# Peripherals.net
KiCad netlist of a schematic drawn in EAGLE
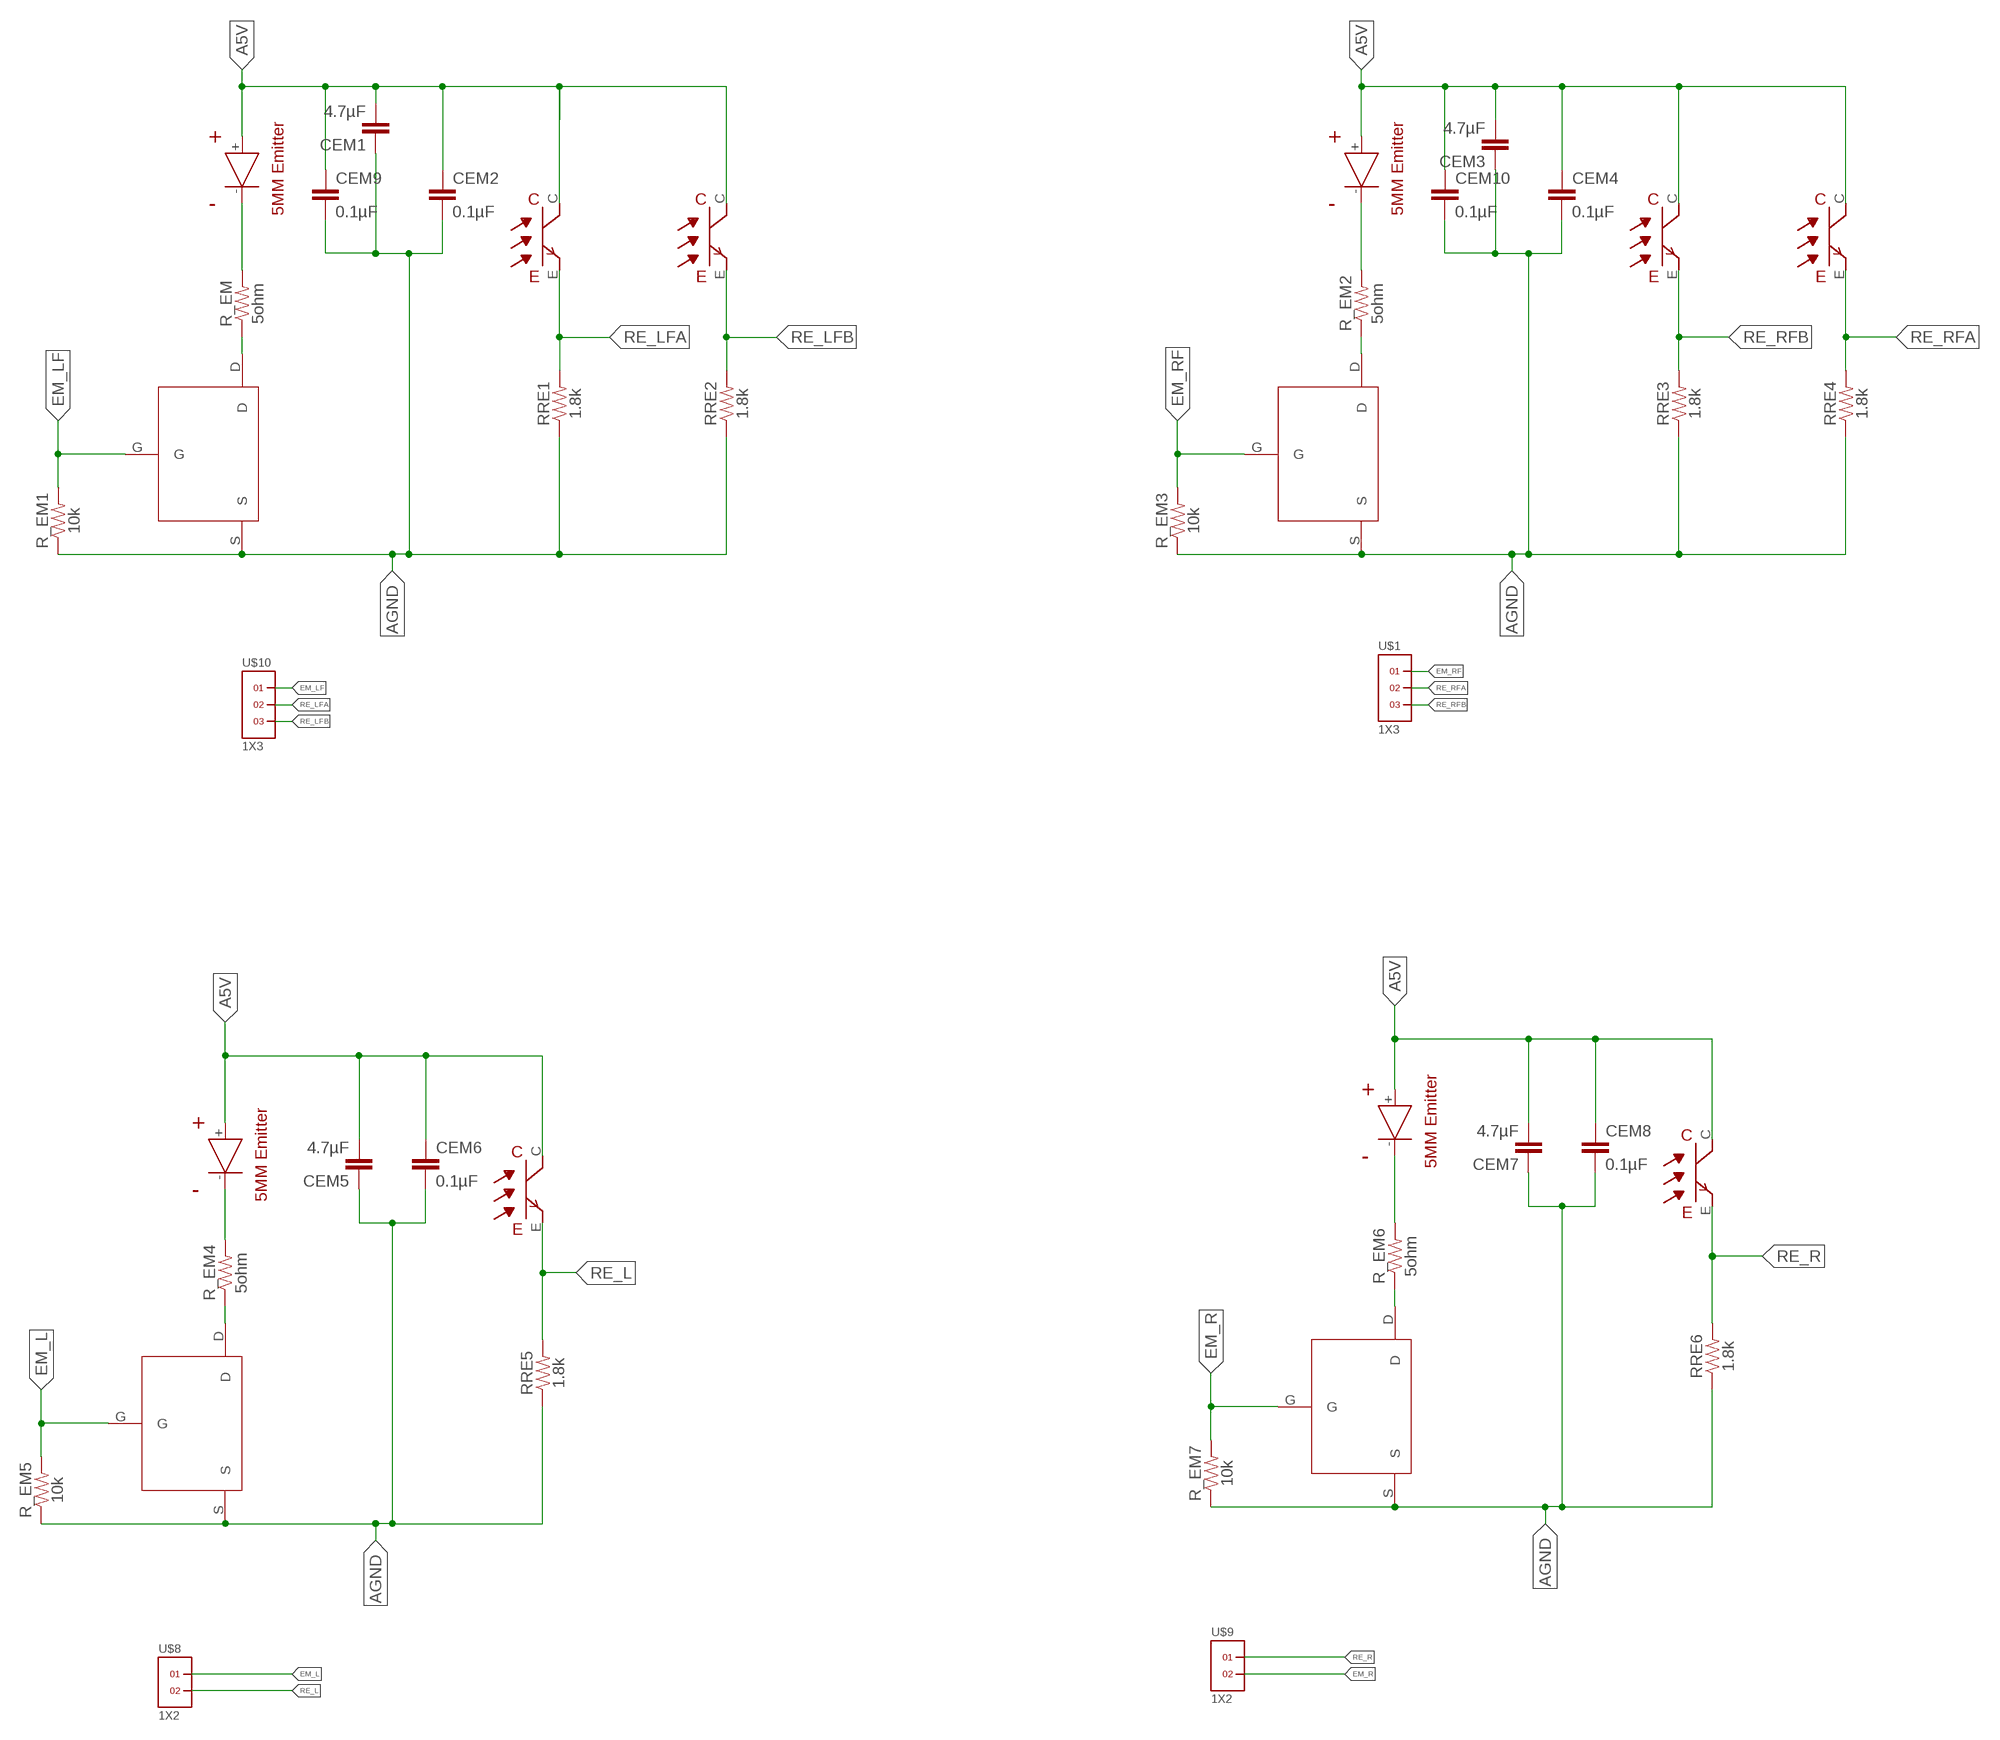
[diagram p0: schematic, sheet 1, part 1 of 2]
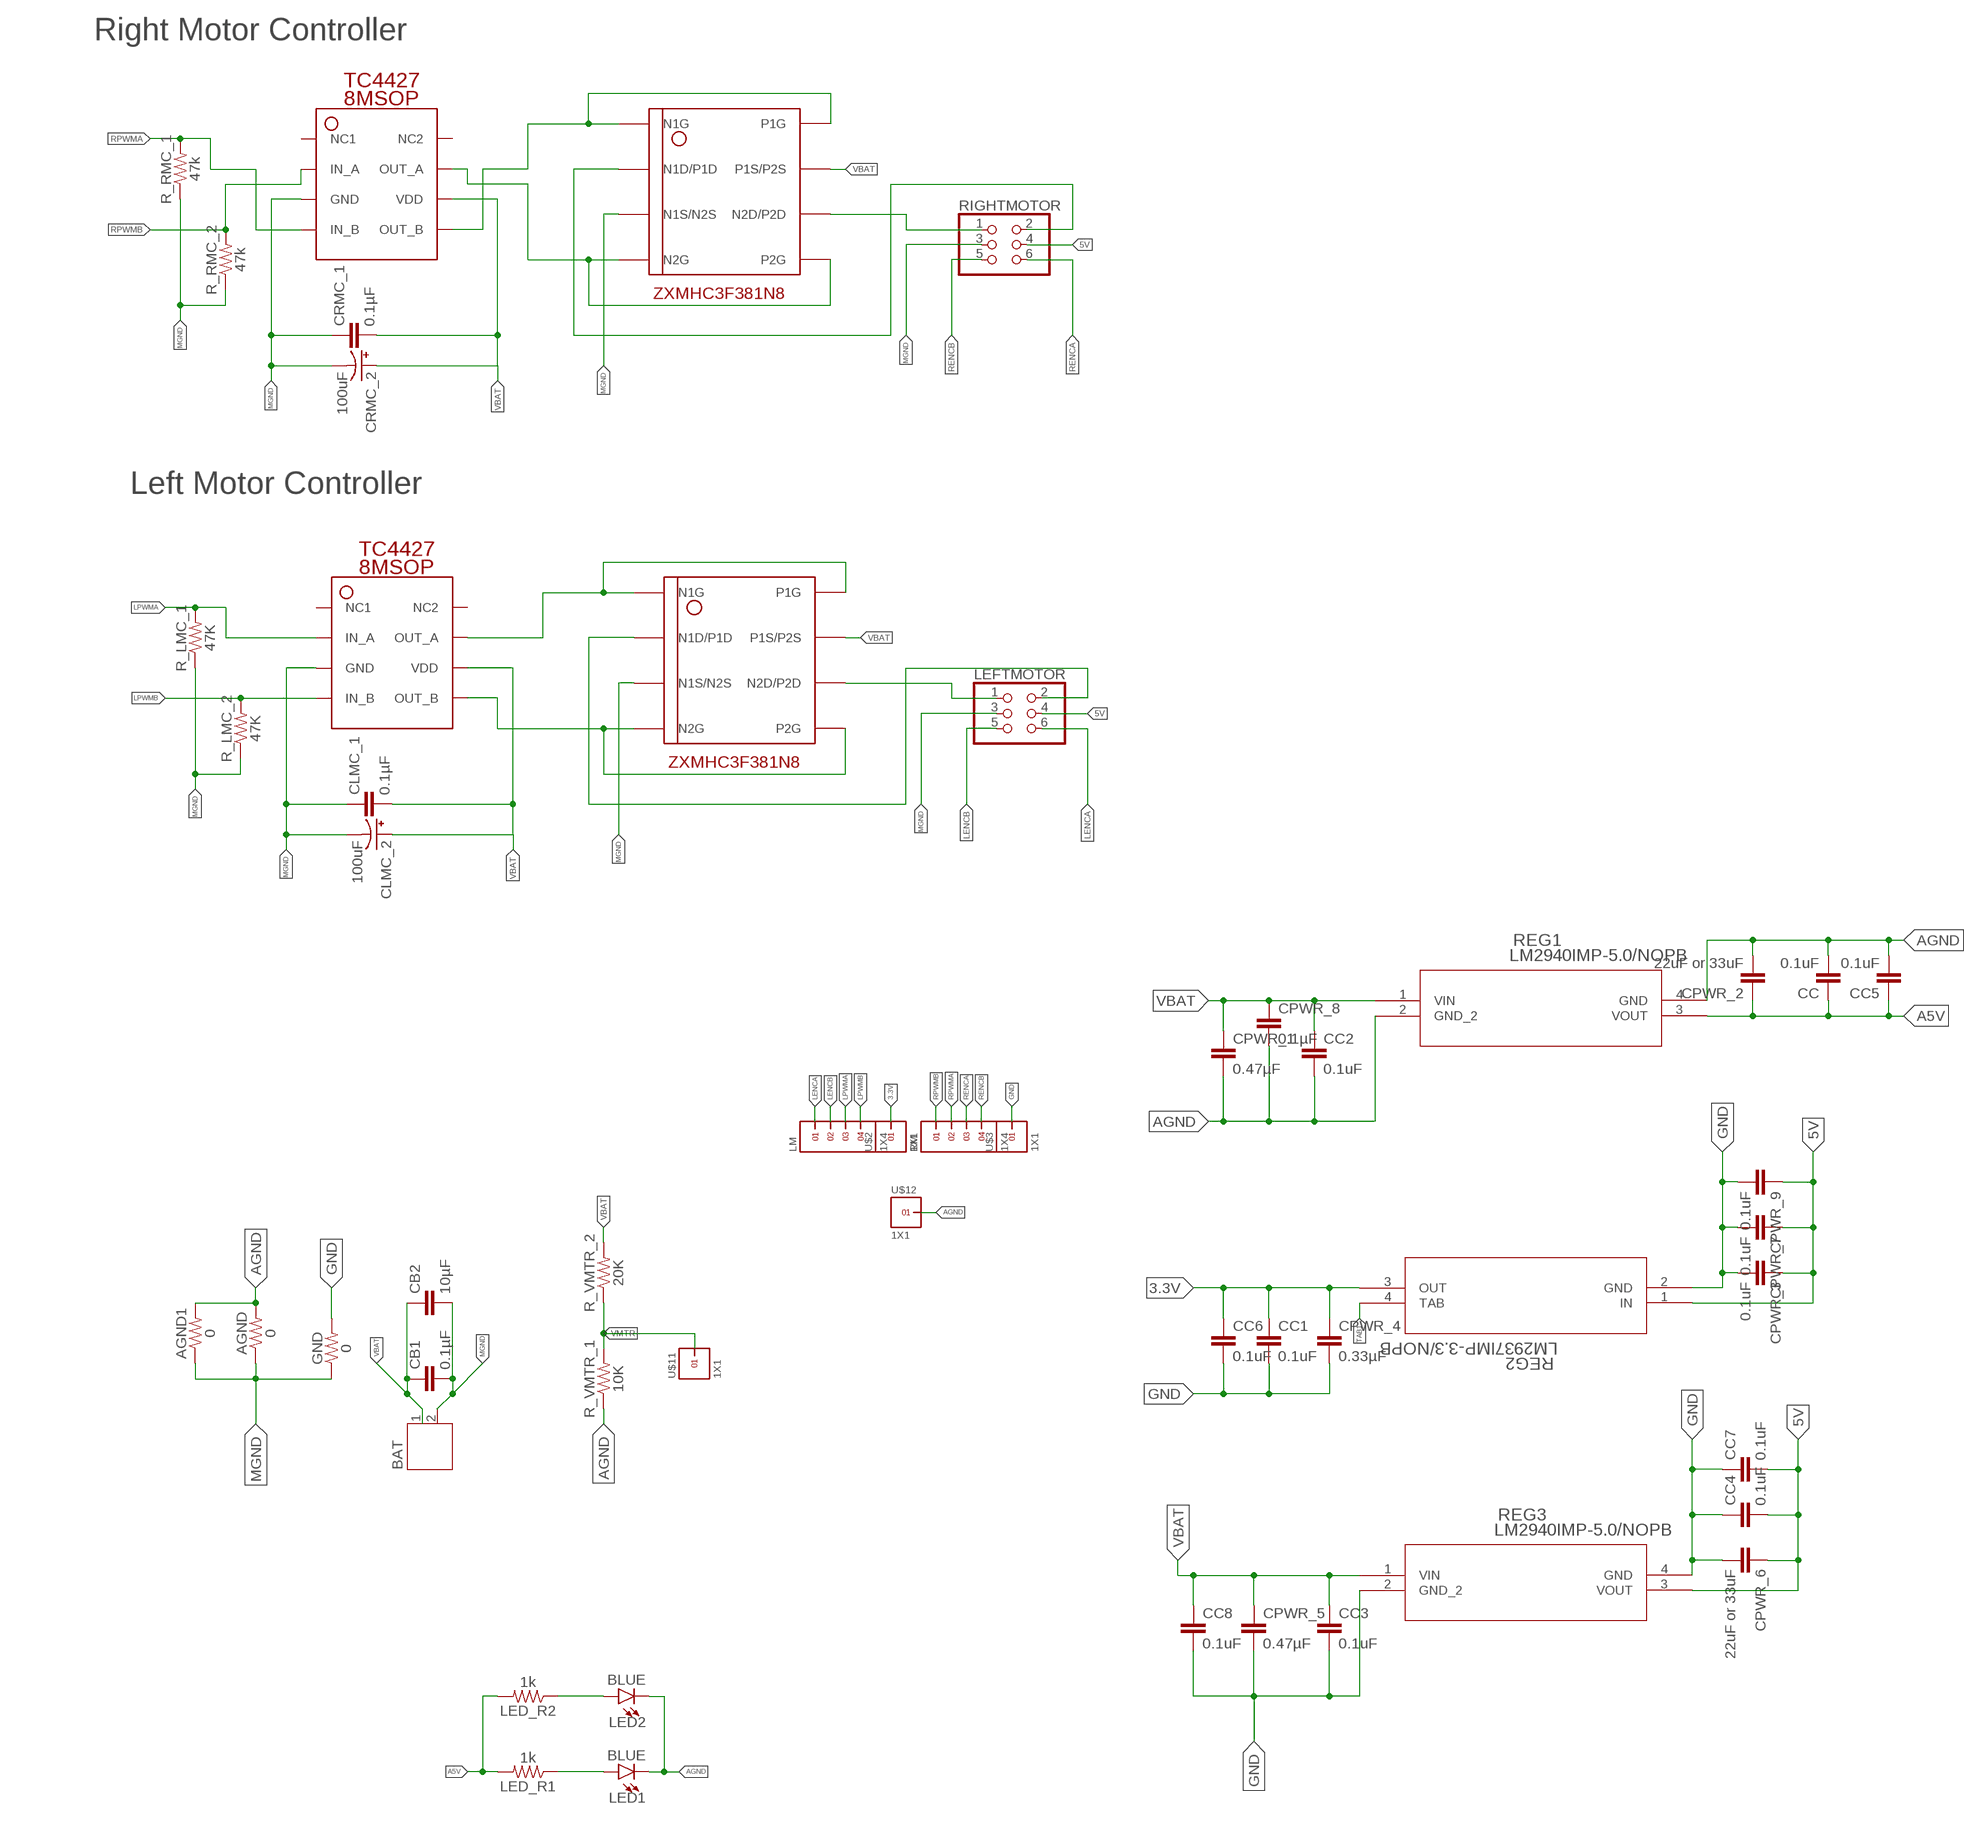
[diagram p1: schematic, sheet 1, part 2 of 2]

(export (version "E")
  (design (tool "Eeschema 10.0.6"))
  (components
    (comp (ref "AGND")
      (value "0")
      (footprint "eagle-import:0805")
      (libsource (lib "eagle-import") (part "SparkFun-Resistors_532_0.75OHM-0805-1/4W-1%"))
    )
    (comp (ref "AGND1")
      (value "0")
      (footprint "eagle-import:0805")
      (libsource (lib "eagle-import") (part "SparkFun-Resistors_532_0.75OHM-0805-1/4W-1%"))
    )
    (comp (ref "BAT")
      (value "JST-PH2")
      (footprint "eagle-import:JST-PH2")
      (libsource (lib "eagle-import") (part "JST-PH2"))
    )
    (comp (ref "CB1")
      (value "0.1µF")
      (footprint "eagle-import:0805")
      (libsource (lib "eagle-import") (part "SparkFun-Capacitors_510_0.33UF/330NF-0805-50V-10%"))
    )
    (comp (ref "CB2")
      (value "10µF")
      (footprint "eagle-import:0805")
      (libsource (lib "eagle-import") (part "SparkFun-Capacitors_510_0.33UF/330NF-0805-50V-10%"))
    )
    (comp (ref "CC")
      (value "0.1uF")
      (footprint "eagle-import:0805")
      (libsource (lib "eagle-import") (part "0.33UF/330NF-0805-50V-10%"))
    )
    (comp (ref "CC1")
      (value "0.1uF")
      (footprint "eagle-import:0805")
      (libsource (lib "eagle-import") (part "0.33UF/330NF-0805-50V-10%"))
    )
    (comp (ref "CC2")
      (value "0.1uF")
      (footprint "eagle-import:0805")
      (libsource (lib "eagle-import") (part "0.33UF/330NF-0805-50V-10%"))
    )
    (comp (ref "CC3")
      (value "0.1uF")
      (footprint "eagle-import:0805")
      (libsource (lib "eagle-import") (part "0.33UF/330NF-0805-50V-10%"))
    )
    (comp (ref "CC4")
      (value "0.1uF")
      (footprint "eagle-import:0805")
      (libsource (lib "eagle-import") (part "0.33UF/330NF-0805-50V-10%"))
    )
    (comp (ref "CC5")
      (value "0.1uF")
      (footprint "eagle-import:0805")
      (libsource (lib "eagle-import") (part "0.33UF/330NF-0805-50V-10%"))
    )
    (comp (ref "CC6")
      (value "0.1uF")
      (footprint "eagle-import:0805")
      (libsource (lib "eagle-import") (part "0.33UF/330NF-0805-50V-10%"))
    )
    (comp (ref "CC7")
      (value "0.1uF")
      (footprint "eagle-import:0805")
      (libsource (lib "eagle-import") (part "0.33UF/330NF-0805-50V-10%"))
    )
    (comp (ref "CC8")
      (value "0.1uF")
      (footprint "eagle-import:0805")
      (libsource (lib "eagle-import") (part "0.33UF/330NF-0805-50V-10%"))
    )
    (comp (ref "CEM1")
      (value "4.7µF")
      (footprint "eagle-import:0805")
      (libsource (lib "eagle-import") (part "0.33UF/330NF-0805-50V-10%"))
    )
    (comp (ref "CEM2")
      (value "0.1µF")
      (footprint "eagle-import:0805")
      (libsource (lib "eagle-import") (part "0.33UF/330NF-0805-50V-10%"))
    )
    (comp (ref "CEM3")
      (value "4.7µF")
      (footprint "eagle-import:0805")
      (libsource (lib "eagle-import") (part "0.33UF/330NF-0805-50V-10%"))
    )
    (comp (ref "CEM4")
      (value "0.1µF")
      (footprint "eagle-import:0805")
      (libsource (lib "eagle-import") (part "0.33UF/330NF-0805-50V-10%"))
    )
    (comp (ref "CEM5")
      (value "4.7µF")
      (footprint "eagle-import:0805")
      (libsource (lib "eagle-import") (part "0.33UF/330NF-0805-50V-10%"))
    )
    (comp (ref "CEM6")
      (value "0.1µF")
      (footprint "eagle-import:0805")
      (libsource (lib "eagle-import") (part "0.33UF/330NF-0805-50V-10%"))
    )
    (comp (ref "CEM7")
      (value "4.7µF")
      (footprint "eagle-import:0805")
      (libsource (lib "eagle-import") (part "0.33UF/330NF-0805-50V-10%"))
    )
    (comp (ref "CEM8")
      (value "0.1µF")
      (footprint "eagle-import:0805")
      (libsource (lib "eagle-import") (part "0.33UF/330NF-0805-50V-10%"))
    )
    (comp (ref "CEM9")
      (value "0.1µF")
      (footprint "eagle-import:0805")
      (libsource (lib "eagle-import") (part "0.33UF/330NF-0805-50V-10%"))
    )
    (comp (ref "CEM10")
      (value "0.1µF")
      (footprint "eagle-import:0805")
      (libsource (lib "eagle-import") (part "0.33UF/330NF-0805-50V-10%"))
    )
    (comp (ref "CLMC_1")
      (value "0.1µF")
      (footprint "eagle-import:0805")
      (libsource (lib "eagle-import") (part "SparkFun-Capacitors_510_0.33UF/330NF-0805-50V-10%"))
    )
    (comp (ref "CLMC_2")
      (value "100uF")
      (footprint "eagle-import:EIA7343")
      (libsource (lib "eagle-import") (part "100UF-POLAR-EIA7343-10V-10%(TANT)"))
    )
    (comp (ref "CPWR_1")
      (value "0.47µF")
      (footprint "eagle-import:0805")
      (libsource (lib "eagle-import") (part "0.33UF/330NF-0805-50V-10%"))
    )
    (comp (ref "CPWR_2")
      (value "22uF or 33uF")
      (footprint "eagle-import:0805")
      (libsource (lib "eagle-import") (part "0.33UF/330NF-0805-50V-10%"))
    )
    (comp (ref "CPWR_3")
      (value "0.1uF")
      (footprint "eagle-import:0805")
      (libsource (lib "eagle-import") (part "0.33UF/330NF-0805-50V-10%"))
    )
    (comp (ref "CPWR_4")
      (value "0.33µF")
      (footprint "eagle-import:0805")
      (libsource (lib "eagle-import") (part "0.33UF/330NF-0805-50V-10%"))
    )
    (comp (ref "CPWR_5")
      (value "0.47µF")
      (footprint "eagle-import:0805")
      (libsource (lib "eagle-import") (part "0.33UF/330NF-0805-50V-10%"))
    )
    (comp (ref "CPWR_6")
      (value "22uF or 33uF")
      (footprint "eagle-import:0805")
      (libsource (lib "eagle-import") (part "0.33UF/330NF-0805-50V-10%"))
    )
    (comp (ref "CPWR_7")
      (value "0.1uF")
      (footprint "eagle-import:0805")
      (libsource (lib "eagle-import") (part "0.33UF/330NF-0805-50V-10%"))
    )
    (comp (ref "CPWR_8")
      (value "0.1µF")
      (footprint "eagle-import:0805")
      (libsource (lib "eagle-import") (part "0.33UF/330NF-0805-50V-10%"))
    )
    (comp (ref "CPWR_9")
      (value "0.1uF")
      (footprint "eagle-import:0805")
      (libsource (lib "eagle-import") (part "0.33UF/330NF-0805-50V-10%"))
    )
    (comp (ref "CRMC_1")
      (value "0.1µF")
      (footprint "eagle-import:0805")
      (libsource (lib "eagle-import") (part "SparkFun-Capacitors_510_0.33UF/330NF-0805-50V-10%"))
    )
    (comp (ref "CRMC_2")
      (value "100uF")
      (footprint "eagle-import:EIA7343")
      (libsource (lib "eagle-import") (part "100UF-POLAR-EIA7343-10V-10%(TANT)"))
    )
    (comp (ref "EM_L")
      (value "EMITTER")
      (footprint "eagle-import:EMITTER")
      (libsource (lib "eagle-import") (part "EMITTER"))
    )
    (comp (ref "EM_LF")
      (value "EMITTER")
      (footprint "eagle-import:EMITTER")
      (libsource (lib "eagle-import") (part "EMITTER"))
    )
    (comp (ref "EM_R")
      (value "EMITTER")
      (footprint "eagle-import:EMITTER")
      (libsource (lib "eagle-import") (part "EMITTER"))
    )
    (comp (ref "EM_RF")
      (value "EMITTER")
      (footprint "eagle-import:EMITTER")
      (libsource (lib "eagle-import") (part "EMITTER"))
    )
    (comp (ref "GND")
      (value "0")
      (footprint "eagle-import:0805")
      (libsource (lib "eagle-import") (part "SparkFun-Resistors_532_0.75OHM-0805-1/4W-1%"))
    )
    (comp (ref "LED1")
      (value "BLUE")
      (footprint "eagle-import:LED-1206")
      (libsource (lib "eagle-import") (part "LED-BLUE1206"))
    )
    (comp (ref "LED2")
      (value "BLUE")
      (footprint "eagle-import:LED-1206")
      (libsource (lib "eagle-import") (part "LED-BLUE1206"))
    )
    (comp (ref "LED_R1")
      (value "1k")
      (footprint "eagle-import:0805")
      (libsource (lib "eagle-import") (part "0.75OHM-0805-1/4W-1%"))
    )
    (comp (ref "LED_R2")
      (value "1k")
      (footprint "eagle-import:0805")
      (libsource (lib "eagle-import") (part "0.75OHM-0805-1/4W-1%"))
    )
    (comp (ref "LEFTMOTOR")
      (value "PINHD-2X3")
      (footprint "eagle-import:2X03")
      (libsource (lib "eagle-import") (part "PINHD-2X3"))
    )
    (comp (ref "LM")
      (value "1X4")
      (footprint "eagle-import:1X4")
      (libsource (lib "eagle-import") (part "1X4"))
    )
    (comp (ref "REG1")
      (value "LM2940IMP-5.0/NOPB")
      (footprint "eagle-import:MP04A")
      (fields
        (field (name "MANUFACTURER_PART_NUMBER") "LM2940IMP5.0NOPB")
        (field (name "COPYRIGHT") "Copyright C 2015 Accelerated Designs. All rights reserved")
      )
      (libsource (lib "eagle-import") (part "LM2940IMP-5.0/NOPB"))
    )
    (comp (ref "REG2")
      (value "LM2937IMP-3.3/NOPB")
      (footprint "eagle-import:MP04A")
      (fields
        (field (name "MANUFACTURER_PART_NUMBER") "lm2937imp3_3nopb")
        (field (name "COPYRIGHT") "Copyright C 2015 Accelerated Designs. All rights reserved")
      )
      (libsource (lib "eagle-import") (part "LM2937IMP-3.3/NOPB"))
    )
    (comp (ref "REG3")
      (value "LM2940IMP-5.0/NOPB")
      (footprint "eagle-import:MP04A")
      (fields
        (field (name "MANUFACTURER_PART_NUMBER") "LM2940IMP5.0NOPB")
        (field (name "COPYRIGHT") "Copyright C 2015 Accelerated Designs. All rights reserved")
      )
      (libsource (lib "eagle-import") (part "LM2940IMP-5.0/NOPB"))
    )
    (comp (ref "RE_L")
      (value "RECEIVER")
      (footprint "eagle-import:RECEIVER")
      (libsource (lib "eagle-import") (part "RECEIVER"))
    )
    (comp (ref "RE_LFA")
      (value "RECEIVER")
      (footprint "eagle-import:RECEIVER")
      (libsource (lib "eagle-import") (part "RECEIVER"))
    )
    (comp (ref "RE_LFB")
      (value "RECEIVER")
      (footprint "eagle-import:RECEIVER")
      (libsource (lib "eagle-import") (part "RECEIVER"))
    )
    (comp (ref "RE_R")
      (value "RECEIVER")
      (footprint "eagle-import:RECEIVER")
      (libsource (lib "eagle-import") (part "RECEIVER"))
    )
    (comp (ref "RE_RFA")
      (value "RECEIVER")
      (footprint "eagle-import:RECEIVER")
      (libsource (lib "eagle-import") (part "RECEIVER"))
    )
    (comp (ref "RE_RFB")
      (value "RECEIVER")
      (footprint "eagle-import:RECEIVER")
      (libsource (lib "eagle-import") (part "RECEIVER"))
    )
    (comp (ref "RIGHTMOTOR")
      (value "PINHD-2X3")
      (footprint "eagle-import:2X03")
      (libsource (lib "eagle-import") (part "PINHD-2X3"))
    )
    (comp (ref "RM")
      (value "1X4")
      (footprint "eagle-import:1X4")
      (libsource (lib "eagle-import") (part "1X4"))
    )
    (comp (ref "RRE1")
      (value "1.8k")
      (footprint "eagle-import:0805")
      (libsource (lib "eagle-import") (part "0.75OHM-0805-1/4W-1%"))
    )
    (comp (ref "RRE2")
      (value "1.8k")
      (footprint "eagle-import:0805")
      (libsource (lib "eagle-import") (part "0.75OHM-0805-1/4W-1%"))
    )
    (comp (ref "RRE3")
      (value "1.8k")
      (footprint "eagle-import:0805")
      (libsource (lib "eagle-import") (part "0.75OHM-0805-1/4W-1%"))
    )
    (comp (ref "RRE4")
      (value "1.8k")
      (footprint "eagle-import:0805")
      (libsource (lib "eagle-import") (part "0.75OHM-0805-1/4W-1%"))
    )
    (comp (ref "RRE5")
      (value "1.8k")
      (footprint "eagle-import:0805")
      (libsource (lib "eagle-import") (part "0.75OHM-0805-1/4W-1%"))
    )
    (comp (ref "RRE6")
      (value "1.8k")
      (footprint "eagle-import:0805")
      (libsource (lib "eagle-import") (part "0.75OHM-0805-1/4W-1%"))
    )
    (comp (ref "R_EM")
      (value "5ohm")
      (footprint "eagle-import:0805")
      (libsource (lib "eagle-import") (part "0.75OHM-0805-1/4W-1%"))
    )
    (comp (ref "R_EM1")
      (value "10k")
      (footprint "eagle-import:0805")
      (libsource (lib "eagle-import") (part "0.75OHM-0805-1/4W-1%"))
    )
    (comp (ref "R_EM2")
      (value "5ohm")
      (footprint "eagle-import:0805")
      (libsource (lib "eagle-import") (part "0.75OHM-0805-1/4W-1%"))
    )
    (comp (ref "R_EM3")
      (value "10k")
      (footprint "eagle-import:0805")
      (libsource (lib "eagle-import") (part "0.75OHM-0805-1/4W-1%"))
    )
    (comp (ref "R_EM4")
      (value "5ohm")
      (footprint "eagle-import:0805")
      (libsource (lib "eagle-import") (part "0.75OHM-0805-1/4W-1%"))
    )
    (comp (ref "R_EM5")
      (value "10k")
      (footprint "eagle-import:0805")
      (libsource (lib "eagle-import") (part "0.75OHM-0805-1/4W-1%"))
    )
    (comp (ref "R_EM6")
      (value "5ohm")
      (footprint "eagle-import:0805")
      (libsource (lib "eagle-import") (part "0.75OHM-0805-1/4W-1%"))
    )
    (comp (ref "R_EM7")
      (value "10k")
      (footprint "eagle-import:0805")
      (libsource (lib "eagle-import") (part "0.75OHM-0805-1/4W-1%"))
    )
    (comp (ref "R_LMC_1")
      (value "47K")
      (footprint "eagle-import:0805")
      (libsource (lib "eagle-import") (part "SparkFun-Resistors_532_0.75OHM-0805-1/4W-1%"))
    )
    (comp (ref "R_LMC_2")
      (value "47K")
      (footprint "eagle-import:0805")
      (libsource (lib "eagle-import") (part "SparkFun-Resistors_532_0.75OHM-0805-1/4W-1%"))
    )
    (comp (ref "R_RMC_1")
      (value "47k")
      (footprint "eagle-import:0805")
      (libsource (lib "eagle-import") (part "SparkFun-Resistors_532_0.75OHM-0805-1/4W-1%"))
    )
    (comp (ref "R_RMC_2")
      (value "47k")
      (footprint "eagle-import:0805")
      (libsource (lib "eagle-import") (part "SparkFun-Resistors_532_0.75OHM-0805-1/4W-1%"))
    )
    (comp (ref "R_VMTR_1")
      (value "10K")
      (footprint "eagle-import:0805")
      (libsource (lib "eagle-import") (part "0.75OHM-0805-1/4W-1%"))
    )
    (comp (ref "R_VMTR_2")
      (value "20K")
      (footprint "eagle-import:0805")
      (libsource (lib "eagle-import") (part "0.75OHM-0805-1/4W-1%"))
    )
    (comp (ref "U$1")
      (value "1X3")
      (footprint "eagle-import:1X3")
      (libsource (lib "eagle-import") (part "1X3"))
    )
    (comp (ref "U$2")
      (value "1X1")
      (footprint "eagle-import:1X1")
      (libsource (lib "eagle-import") (part "1X1"))
    )
    (comp (ref "U$3")
      (value "1X1")
      (footprint "eagle-import:1X1")
      (libsource (lib "eagle-import") (part "1X1"))
    )
    (comp (ref "U$4")
      (value "MCH3474")
      (footprint "eagle-import:MCH3474")
      (libsource (lib "eagle-import") (part "MCH3474"))
    )
    (comp (ref "U$5")
      (value "MCH3474")
      (footprint "eagle-import:MCH3474")
      (libsource (lib "eagle-import") (part "MCH3474"))
    )
    (comp (ref "U$6")
      (value "MCH3474")
      (footprint "eagle-import:MCH3474")
      (libsource (lib "eagle-import") (part "MCH3474"))
    )
    (comp (ref "U$7")
      (value "MCH3474")
      (footprint "eagle-import:MCH3474")
      (libsource (lib "eagle-import") (part "MCH3474"))
    )
    (comp (ref "U$8")
      (value "1X2")
      (footprint "eagle-import:1X2")
      (libsource (lib "eagle-import") (part "1X2"))
    )
    (comp (ref "U$9")
      (value "1X2")
      (footprint "eagle-import:1X2")
      (libsource (lib "eagle-import") (part "1X2"))
    )
    (comp (ref "U$10")
      (value "1X3")
      (footprint "eagle-import:1X3")
      (libsource (lib "eagle-import") (part "1X3"))
    )
    (comp (ref "U$11")
      (value "1X1")
      (footprint "eagle-import:1X1")
      (libsource (lib "eagle-import") (part "1X1"))
    )
    (comp (ref "U$12")
      (value "1X1")
      (footprint "eagle-import:1X1")
      (libsource (lib "eagle-import") (part "1X1"))
    )
    (comp (ref "U$15")
      (value "TC4427(8MSOP)")
      (footprint "eagle-import:TC4427(8MSOP)")
      (libsource (lib "eagle-import") (part "TC4427(8MSOP)"))
    )
    (comp (ref "U$16")
      (value "ZXMHC3F381N8")
      (footprint "eagle-import:ZXMHC3F381N8")
      (libsource (lib "eagle-import") (part "ZXMHC3F381N8"))
    )
    (comp (ref "U$17")
      (value "TC4427(8MSOP)")
      (footprint "eagle-import:TC4427(8MSOP)")
      (libsource (lib "eagle-import") (part "TC4427(8MSOP)"))
    )
    (comp (ref "U$18")
      (value "ZXMHC3F381N8")
      (footprint "eagle-import:ZXMHC3F381N8")
      (libsource (lib "eagle-import") (part "ZXMHC3F381N8"))
    )
  )
  (nets
    (net (code "1") (name "3.3V") (class "Default")
      (node (ref "CC1") (pin "1") (pinfunction "1_1") (pintype "passive"))
      (node (ref "CC6") (pin "1") (pinfunction "1_1") (pintype "passive"))
      (node (ref "CPWR_4") (pin "1") (pinfunction "1_1") (pintype "passive"))
      (node (ref "REG2") (pin "3") (pinfunction "OUT_3") (pintype "power_in"))
      (node (ref "U$2") (pin "1") (pinfunction "1_1") (pintype "bidirectional"))
    )
    (net (code "2") (name "5V") (class "Default")
      (node (ref "CC4") (pin "2") (pinfunction "2_2") (pintype "passive"))
      (node (ref "CC7") (pin "2") (pinfunction "2_2") (pintype "passive"))
      (node (ref "CPWR_3") (pin "1") (pinfunction "1_1") (pintype "passive"))
      (node (ref "CPWR_6") (pin "1") (pinfunction "1_1") (pintype "passive"))
      (node (ref "CPWR_7") (pin "1") (pinfunction "1_1") (pintype "passive"))
      (node (ref "CPWR_9") (pin "1") (pinfunction "1_1") (pintype "passive"))
      (node (ref "LEFTMOTOR") (pin "4") (pinfunction "4_4") (pintype "passive"))
      (node (ref "REG2") (pin "1") (pinfunction "IN_1") (pintype "power_in"))
      (node (ref "REG3") (pin "3") (pinfunction "VOUT_3") (pintype "output"))
      (node (ref "RIGHTMOTOR") (pin "4") (pinfunction "4_4") (pintype "passive"))
    )
    (net (code "3") (name "A5V") (class "Default")
      (node (ref "CC") (pin "1") (pinfunction "1_1") (pintype "passive"))
      (node (ref "CC5") (pin "1") (pinfunction "1_1") (pintype "passive"))
      (node (ref "CEM1") (pin "2") (pinfunction "2_2") (pintype "passive"))
      (node (ref "CEM10") (pin "1") (pinfunction "1_1") (pintype "passive"))
      (node (ref "CEM2") (pin "1") (pinfunction "1_1") (pintype "passive"))
      (node (ref "CEM3") (pin "2") (pinfunction "2_2") (pintype "passive"))
      (node (ref "CEM4") (pin "1") (pinfunction "1_1") (pintype "passive"))
      (node (ref "CEM5") (pin "2") (pinfunction "2_2") (pintype "passive"))
      (node (ref "CEM6") (pin "1") (pinfunction "1_1") (pintype "passive"))
      (node (ref "CEM7") (pin "2") (pinfunction "2_2") (pintype "passive"))
      (node (ref "CEM8") (pin "1") (pinfunction "1_1") (pintype "passive"))
      (node (ref "CEM9") (pin "1") (pinfunction "1_1") (pintype "passive"))
      (node (ref "CPWR_2") (pin "1") (pinfunction "1_1") (pintype "passive"))
      (node (ref "EM_L") (pin "+") (pinfunction "+_+") (pintype "bidirectional"))
      (node (ref "EM_LF") (pin "+") (pinfunction "+_+") (pintype "bidirectional"))
      (node (ref "EM_R") (pin "+") (pinfunction "+_+") (pintype "bidirectional"))
      (node (ref "EM_RF") (pin "+") (pinfunction "+_+") (pintype "bidirectional"))
      (node (ref "LED_R1") (pin "2") (pinfunction "2_2") (pintype "passive"))
      (node (ref "LED_R2") (pin "2") (pinfunction "2_2") (pintype "passive"))
      (node (ref "REG1") (pin "3") (pinfunction "VOUT_3") (pintype "output"))
      (node (ref "RE_L") (pin "C") (pinfunction "C_C") (pintype "bidirectional"))
      (node (ref "RE_LFA") (pin "C") (pinfunction "C_C") (pintype "bidirectional"))
      (node (ref "RE_LFB") (pin "C") (pinfunction "C_C") (pintype "bidirectional"))
      (node (ref "RE_R") (pin "C") (pinfunction "C_C") (pintype "bidirectional"))
      (node (ref "RE_RFA") (pin "C") (pinfunction "C_C") (pintype "bidirectional"))
      (node (ref "RE_RFB") (pin "C") (pinfunction "C_C") (pintype "bidirectional"))
    )
    (net (code "4") (name "AGND") (class "Default")
      (node (ref "AGND") (pin "2") (pinfunction "2_2") (pintype "passive"))
      (node (ref "AGND1") (pin "2") (pinfunction "2_2") (pintype "passive"))
      (node (ref "CC") (pin "2") (pinfunction "2_2") (pintype "passive"))
      (node (ref "CC2") (pin "2") (pinfunction "2_2") (pintype "passive"))
      (node (ref "CC5") (pin "2") (pinfunction "2_2") (pintype "passive"))
      (node (ref "CEM1") (pin "1") (pinfunction "1_1") (pintype "passive"))
      (node (ref "CEM10") (pin "2") (pinfunction "2_2") (pintype "passive"))
      (node (ref "CEM2") (pin "2") (pinfunction "2_2") (pintype "passive"))
      (node (ref "CEM3") (pin "1") (pinfunction "1_1") (pintype "passive"))
      (node (ref "CEM4") (pin "2") (pinfunction "2_2") (pintype "passive"))
      (node (ref "CEM5") (pin "1") (pinfunction "1_1") (pintype "passive"))
      (node (ref "CEM6") (pin "2") (pinfunction "2_2") (pintype "passive"))
      (node (ref "CEM7") (pin "1") (pinfunction "1_1") (pintype "passive"))
      (node (ref "CEM8") (pin "2") (pinfunction "2_2") (pintype "passive"))
      (node (ref "CEM9") (pin "2") (pinfunction "2_2") (pintype "passive"))
      (node (ref "CPWR_1") (pin "2") (pinfunction "2_2") (pintype "passive"))
      (node (ref "CPWR_2") (pin "2") (pinfunction "2_2") (pintype "passive"))
      (node (ref "CPWR_8") (pin "2") (pinfunction "2_2") (pintype "passive"))
      (node (ref "LED1") (pin "C") (pinfunction "C_C") (pintype "passive"))
      (node (ref "LED2") (pin "C") (pinfunction "C_C") (pintype "passive"))
      (node (ref "REG1") (pin "2") (pinfunction "GND_2_2") (pintype "power_in"))
      (node (ref "REG1") (pin "4") (pinfunction "GND_4") (pintype "power_in"))
      (node (ref "RRE1") (pin "1") (pinfunction "1_1") (pintype "passive"))
      (node (ref "RRE2") (pin "1") (pinfunction "1_1") (pintype "passive"))
      (node (ref "RRE3") (pin "1") (pinfunction "1_1") (pintype "passive"))
      (node (ref "RRE4") (pin "1") (pinfunction "1_1") (pintype "passive"))
      (node (ref "RRE5") (pin "1") (pinfunction "1_1") (pintype "passive"))
      (node (ref "RRE6") (pin "1") (pinfunction "1_1") (pintype "passive"))
      (node (ref "R_EM1") (pin "1") (pinfunction "1_1") (pintype "passive"))
      (node (ref "R_EM3") (pin "1") (pinfunction "1_1") (pintype "passive"))
      (node (ref "R_EM5") (pin "1") (pinfunction "1_1") (pintype "passive"))
      (node (ref "R_EM7") (pin "1") (pinfunction "1_1") (pintype "passive"))
      (node (ref "R_VMTR_1") (pin "1") (pinfunction "1_1") (pintype "passive"))
      (node (ref "U$12") (pin "1") (pinfunction "1_1") (pintype "bidirectional"))
      (node (ref "U$4") (pin "S") (pinfunction "S_S") (pintype "bidirectional"))
      (node (ref "U$5") (pin "S") (pinfunction "S_S") (pintype "bidirectional"))
      (node (ref "U$6") (pin "S") (pinfunction "S_S") (pintype "bidirectional"))
      (node (ref "U$7") (pin "S") (pinfunction "S_S") (pintype "bidirectional"))
    )
    (net (code "5") (name "EM_L") (class "Default")
      (node (ref "R_EM5") (pin "2") (pinfunction "2_2") (pintype "passive"))
      (node (ref "U$4") (pin "G") (pinfunction "G_G") (pintype "bidirectional"))
      (node (ref "U$8") (pin "1") (pinfunction "1_1") (pintype "bidirectional"))
    )
    (net (code "6") (name "EM_LF") (class "Default")
      (node (ref "R_EM1") (pin "2") (pinfunction "2_2") (pintype "passive"))
      (node (ref "U$10") (pin "1") (pinfunction "1_1") (pintype "bidirectional"))
      (node (ref "U$5") (pin "G") (pinfunction "G_G") (pintype "bidirectional"))
    )
    (net (code "7") (name "EM_R") (class "Default")
      (node (ref "R_EM7") (pin "2") (pinfunction "2_2") (pintype "passive"))
      (node (ref "U$7") (pin "G") (pinfunction "G_G") (pintype "bidirectional"))
      (node (ref "U$9") (pin "2") (pinfunction "2_2") (pintype "bidirectional"))
    )
    (net (code "8") (name "EM_RF") (class "Default")
      (node (ref "R_EM3") (pin "2") (pinfunction "2_2") (pintype "passive"))
      (node (ref "U$1") (pin "1") (pinfunction "1_1") (pintype "bidirectional"))
      (node (ref "U$6") (pin "G") (pinfunction "G_G") (pintype "bidirectional"))
    )
    (net (code "9") (name "GND") (class "Default")
      (node (ref "CC1") (pin "2") (pinfunction "2_2") (pintype "passive"))
      (node (ref "CC3") (pin "2") (pinfunction "2_2") (pintype "passive"))
      (node (ref "CC4") (pin "1") (pinfunction "1_1") (pintype "passive"))
      (node (ref "CC6") (pin "2") (pinfunction "2_2") (pintype "passive"))
      (node (ref "CC7") (pin "1") (pinfunction "1_1") (pintype "passive"))
      (node (ref "CC8") (pin "2") (pinfunction "2_2") (pintype "passive"))
      (node (ref "CPWR_3") (pin "2") (pinfunction "2_2") (pintype "passive"))
      (node (ref "CPWR_4") (pin "2") (pinfunction "2_2") (pintype "passive"))
      (node (ref "CPWR_5") (pin "2") (pinfunction "2_2") (pintype "passive"))
      (node (ref "CPWR_6") (pin "2") (pinfunction "2_2") (pintype "passive"))
      (node (ref "CPWR_7") (pin "2") (pinfunction "2_2") (pintype "passive"))
      (node (ref "CPWR_9") (pin "2") (pinfunction "2_2") (pintype "passive"))
      (node (ref "GND") (pin "2") (pinfunction "2_2") (pintype "passive"))
      (node (ref "REG2") (pin "2") (pinfunction "GND_2") (pintype "power_in"))
      (node (ref "REG3") (pin "2") (pinfunction "GND_2_2") (pintype "power_in"))
      (node (ref "REG3") (pin "4") (pinfunction "GND_4") (pintype "power_in"))
      (node (ref "U$3") (pin "1") (pinfunction "1_1") (pintype "bidirectional"))
    )
    (net (code "10") (name "LENCA") (class "Default")
      (node (ref "LEFTMOTOR") (pin "6") (pinfunction "6_6") (pintype "passive"))
      (node (ref "LM") (pin "1") (pinfunction "1_1") (pintype "bidirectional"))
    )
    (net (code "11") (name "LENCB") (class "Default")
      (node (ref "LEFTMOTOR") (pin "5") (pinfunction "5_5") (pintype "passive"))
      (node (ref "LM") (pin "2") (pinfunction "2_2") (pintype "bidirectional"))
    )
    (net (code "12") (name "LPWMA") (class "Default")
      (node (ref "LM") (pin "3") (pinfunction "3_3") (pintype "bidirectional"))
      (node (ref "R_LMC_1") (pin "2") (pinfunction "2_2") (pintype "passive"))
      (node (ref "U$15") (pin "IN_A") (pinfunction "IN_A_IN_A") (pintype "bidirectional"))
    )
    (net (code "13") (name "LPWMB") (class "Default")
      (node (ref "LM") (pin "4") (pinfunction "4_4") (pintype "bidirectional"))
      (node (ref "R_LMC_2") (pin "2") (pinfunction "2_2") (pintype "passive"))
      (node (ref "U$15") (pin "IN_B") (pinfunction "IN_B_IN_B") (pintype "bidirectional"))
    )
    (net (code "14") (name "MGND") (class "Default")
      (node (ref "AGND") (pin "1") (pinfunction "1_1") (pintype "passive"))
      (node (ref "AGND1") (pin "1") (pinfunction "1_1") (pintype "passive"))
      (node (ref "BAT") (pin "2") (pinfunction "2_2") (pintype "passive"))
      (node (ref "CB1") (pin "2") (pinfunction "2_2") (pintype "passive"))
      (node (ref "CB2") (pin "2") (pinfunction "2_2") (pintype "passive"))
      (node (ref "CLMC_1") (pin "1") (pinfunction "1_1") (pintype "passive"))
      (node (ref "CLMC_2") (pin "C") (pinfunction "-_C") (pintype "passive"))
      (node (ref "CRMC_1") (pin "1") (pinfunction "1_1") (pintype "passive"))
      (node (ref "CRMC_2") (pin "C") (pinfunction "-_C") (pintype "passive"))
      (node (ref "GND") (pin "1") (pinfunction "1_1") (pintype "passive"))
      (node (ref "LEFTMOTOR") (pin "3") (pinfunction "3_3") (pintype "passive"))
      (node (ref "RIGHTMOTOR") (pin "3") (pinfunction "3_3") (pintype "passive"))
      (node (ref "R_LMC_1") (pin "1") (pinfunction "1_1") (pintype "passive"))
      (node (ref "R_LMC_2") (pin "1") (pinfunction "1_1") (pintype "passive"))
      (node (ref "R_RMC_1") (pin "1") (pinfunction "1_1") (pintype "passive"))
      (node (ref "R_RMC_2") (pin "1") (pinfunction "1_1") (pintype "passive"))
      (node (ref "U$15") (pin "GND") (pinfunction "GND_GND") (pintype "bidirectional"))
      (node (ref "U$16") (pin "N1S/N2S") (pinfunction "N1S/N2S_N1S/N2S") (pintype "bidirectional"))
      (node (ref "U$17") (pin "GND") (pinfunction "GND_GND") (pintype "bidirectional"))
      (node (ref "U$18") (pin "N1S/N2S") (pinfunction "N1S/N2S_N1S/N2S") (pintype "bidirectional"))
    )
    (net (code "15") (name "Net-(EM_L-Pad-)") (class "Default")
      (node (ref "EM_L") (pin "-") (pinfunction "-_-") (pintype "bidirectional"))
      (node (ref "R_EM4") (pin "2") (pinfunction "2_2") (pintype "passive"))
    )
    (net (code "16") (name "Net-(EM_LF-Pad-)") (class "Default")
      (node (ref "EM_LF") (pin "-") (pinfunction "-_-") (pintype "bidirectional"))
      (node (ref "R_EM") (pin "2") (pinfunction "2_2") (pintype "passive"))
    )
    (net (code "17") (name "Net-(EM_R-Pad-)") (class "Default")
      (node (ref "EM_R") (pin "-") (pinfunction "-_-") (pintype "bidirectional"))
      (node (ref "R_EM6") (pin "2") (pinfunction "2_2") (pintype "passive"))
    )
    (net (code "18") (name "Net-(EM_RF-Pad-)") (class "Default")
      (node (ref "EM_RF") (pin "-") (pinfunction "-_-") (pintype "bidirectional"))
      (node (ref "R_EM2") (pin "2") (pinfunction "2_2") (pintype "passive"))
    )
    (net (code "19") (name "Net-(LED1-PadA)") (class "Default")
      (node (ref "LED1") (pin "A") (pinfunction "A_A") (pintype "passive"))
      (node (ref "LED_R1") (pin "1") (pinfunction "1_1") (pintype "passive"))
    )
    (net (code "20") (name "Net-(LED2-PadA)") (class "Default")
      (node (ref "LED2") (pin "A") (pinfunction "A_A") (pintype "passive"))
      (node (ref "LED_R2") (pin "1") (pinfunction "1_1") (pintype "passive"))
    )
    (net (code "21") (name "Net-(LEFTMOTOR-Pad1)") (class "Default")
      (node (ref "LEFTMOTOR") (pin "1") (pinfunction "1_1") (pintype "passive"))
      (node (ref "U$16") (pin "N2D/P2D") (pinfunction "N2D/P2D_N2D/P2D") (pintype "bidirectional"))
    )
    (net (code "22") (name "Net-(LEFTMOTOR-Pad2)") (class "Default")
      (node (ref "LEFTMOTOR") (pin "2") (pinfunction "2_2") (pintype "passive"))
      (node (ref "U$16") (pin "N1D/P1D") (pinfunction "N1D/P1D_N1D/P1D") (pintype "bidirectional"))
    )
    (net (code "23") (name "Net-(RIGHTMOTOR-Pad1)") (class "Default")
      (node (ref "RIGHTMOTOR") (pin "1") (pinfunction "1_1") (pintype "passive"))
      (node (ref "U$18") (pin "N2D/P2D") (pinfunction "N2D/P2D_N2D/P2D") (pintype "bidirectional"))
    )
    (net (code "24") (name "Net-(RIGHTMOTOR-Pad2)") (class "Default")
      (node (ref "RIGHTMOTOR") (pin "2") (pinfunction "2_2") (pintype "passive"))
      (node (ref "U$18") (pin "N1D/P1D") (pinfunction "N1D/P1D_N1D/P1D") (pintype "bidirectional"))
    )
    (net (code "25") (name "Net-(R_EM-Pad1)") (class "Default")
      (node (ref "R_EM") (pin "1") (pinfunction "1_1") (pintype "passive"))
      (node (ref "U$5") (pin "D") (pinfunction "D_D") (pintype "bidirectional"))
    )
    (net (code "26") (name "Net-(R_EM2-Pad1)") (class "Default")
      (node (ref "R_EM2") (pin "1") (pinfunction "1_1") (pintype "passive"))
      (node (ref "U$6") (pin "D") (pinfunction "D_D") (pintype "bidirectional"))
    )
    (net (code "27") (name "Net-(R_EM4-Pad1)") (class "Default")
      (node (ref "R_EM4") (pin "1") (pinfunction "1_1") (pintype "passive"))
      (node (ref "U$4") (pin "D") (pinfunction "D_D") (pintype "bidirectional"))
    )
    (net (code "28") (name "Net-(R_EM6-Pad1)") (class "Default")
      (node (ref "R_EM6") (pin "1") (pinfunction "1_1") (pintype "passive"))
      (node (ref "U$7") (pin "D") (pinfunction "D_D") (pintype "bidirectional"))
    )
    (net (code "29") (name "Net-(U$15-PadOUT_A)") (class "Default")
      (node (ref "U$15") (pin "OUT_A") (pinfunction "OUT_A_OUT_A") (pintype "bidirectional"))
      (node (ref "U$16") (pin "N1G") (pinfunction "N1G_N1G") (pintype "bidirectional"))
      (node (ref "U$16") (pin "P1G") (pinfunction "P1G_P1G") (pintype "bidirectional"))
    )
    (net (code "30") (name "Net-(U$15-PadOUT_B)") (class "Default")
      (node (ref "U$15") (pin "OUT_B") (pinfunction "OUT_B_OUT_B") (pintype "bidirectional"))
      (node (ref "U$16") (pin "N2G") (pinfunction "N2G_N2G") (pintype "bidirectional"))
      (node (ref "U$16") (pin "P2G") (pinfunction "P2G_P2G") (pintype "bidirectional"))
    )
    (net (code "31") (name "Net-(U$17-PadOUT_A)") (class "Default")
      (node (ref "U$17") (pin "OUT_A") (pinfunction "OUT_A_OUT_A") (pintype "bidirectional"))
      (node (ref "U$18") (pin "N2G") (pinfunction "N2G_N2G") (pintype "bidirectional"))
      (node (ref "U$18") (pin "P2G") (pinfunction "P2G_P2G") (pintype "bidirectional"))
    )
    (net (code "32") (name "Net-(U$17-PadOUT_B)") (class "Default")
      (node (ref "U$17") (pin "OUT_B") (pinfunction "OUT_B_OUT_B") (pintype "bidirectional"))
      (node (ref "U$18") (pin "N1G") (pinfunction "N1G_N1G") (pintype "bidirectional"))
      (node (ref "U$18") (pin "P1G") (pinfunction "P1G_P1G") (pintype "bidirectional"))
    )
    (net (code "33") (name "RENCA") (class "Default")
      (node (ref "RIGHTMOTOR") (pin "6") (pinfunction "6_6") (pintype "passive"))
      (node (ref "RM") (pin "3") (pinfunction "3_3") (pintype "bidirectional"))
    )
    (net (code "34") (name "RENCB") (class "Default")
      (node (ref "RIGHTMOTOR") (pin "5") (pinfunction "5_5") (pintype "passive"))
      (node (ref "RM") (pin "4") (pinfunction "4_4") (pintype "bidirectional"))
    )
    (net (code "35") (name "RE_L") (class "Default")
      (node (ref "RE_L") (pin "E") (pinfunction "E_E") (pintype "bidirectional"))
      (node (ref "RRE5") (pin "2") (pinfunction "2_2") (pintype "passive"))
      (node (ref "U$8") (pin "2") (pinfunction "2_2") (pintype "bidirectional"))
    )
    (net (code "36") (name "RE_LFA") (class "Default")
      (node (ref "RE_LFA") (pin "E") (pinfunction "E_E") (pintype "bidirectional"))
      (node (ref "RRE1") (pin "2") (pinfunction "2_2") (pintype "passive"))
      (node (ref "U$10") (pin "2") (pinfunction "2_2") (pintype "bidirectional"))
    )
    (net (code "37") (name "RE_LFB") (class "Default")
      (node (ref "RE_LFB") (pin "E") (pinfunction "E_E") (pintype "bidirectional"))
      (node (ref "RRE2") (pin "2") (pinfunction "2_2") (pintype "passive"))
      (node (ref "U$10") (pin "3") (pinfunction "3_3") (pintype "bidirectional"))
    )
    (net (code "38") (name "RE_R") (class "Default")
      (node (ref "RE_R") (pin "E") (pinfunction "E_E") (pintype "bidirectional"))
      (node (ref "RRE6") (pin "2") (pinfunction "2_2") (pintype "passive"))
      (node (ref "U$9") (pin "1") (pinfunction "1_1") (pintype "bidirectional"))
    )
    (net (code "39") (name "RE_RFA") (class "Default")
      (node (ref "RE_RFB") (pin "E") (pinfunction "E_E") (pintype "bidirectional"))
      (node (ref "RRE4") (pin "2") (pinfunction "2_2") (pintype "passive"))
      (node (ref "U$1") (pin "2") (pinfunction "2_2") (pintype "bidirectional"))
    )
    (net (code "40") (name "RE_RFB") (class "Default")
      (node (ref "RE_RFA") (pin "E") (pinfunction "E_E") (pintype "bidirectional"))
      (node (ref "RRE3") (pin "2") (pinfunction "2_2") (pintype "passive"))
      (node (ref "U$1") (pin "3") (pinfunction "3_3") (pintype "bidirectional"))
    )
    (net (code "41") (name "RPWMA") (class "Default")
      (node (ref "RM") (pin "2") (pinfunction "2_2") (pintype "bidirectional"))
      (node (ref "R_RMC_1") (pin "2") (pinfunction "2_2") (pintype "passive"))
      (node (ref "U$17") (pin "IN_B") (pinfunction "IN_B_IN_B") (pintype "bidirectional"))
    )
    (net (code "42") (name "RPWMB") (class "Default")
      (node (ref "RM") (pin "1") (pinfunction "1_1") (pintype "bidirectional"))
      (node (ref "R_RMC_2") (pin "2") (pinfunction "2_2") (pintype "passive"))
      (node (ref "U$17") (pin "IN_A") (pinfunction "IN_A_IN_A") (pintype "bidirectional"))
    )
    (net (code "43") (name "TAB1") (class "Default")
      (node (ref "REG2") (pin "4") (pinfunction "TAB_4") (pintype "power_in"))
    )
    (net (code "44") (name "VBAT") (class "Default")
      (node (ref "BAT") (pin "1") (pinfunction "1_1") (pintype "passive"))
      (node (ref "CB1") (pin "1") (pinfunction "1_1") (pintype "passive"))
      (node (ref "CB2") (pin "1") (pinfunction "1_1") (pintype "passive"))
      (node (ref "CC2") (pin "1") (pinfunction "1_1") (pintype "passive"))
      (node (ref "CC3") (pin "1") (pinfunction "1_1") (pintype "passive"))
      (node (ref "CC8") (pin "1") (pinfunction "1_1") (pintype "passive"))
      (node (ref "CLMC_1") (pin "2") (pinfunction "2_2") (pintype "passive"))
      (node (ref "CLMC_2") (pin "A") (pinfunction "+_A") (pintype "passive"))
      (node (ref "CPWR_1") (pin "1") (pinfunction "1_1") (pintype "passive"))
      (node (ref "CPWR_5") (pin "1") (pinfunction "1_1") (pintype "passive"))
      (node (ref "CPWR_8") (pin "1") (pinfunction "1_1") (pintype "passive"))
      (node (ref "CRMC_1") (pin "2") (pinfunction "2_2") (pintype "passive"))
      (node (ref "CRMC_2") (pin "A") (pinfunction "+_A") (pintype "passive"))
      (node (ref "REG1") (pin "1") (pinfunction "VIN_1") (pintype "input"))
      (node (ref "REG3") (pin "1") (pinfunction "VIN_1") (pintype "input"))
      (node (ref "R_VMTR_2") (pin "2") (pinfunction "2_2") (pintype "passive"))
      (node (ref "U$15") (pin "VDD") (pinfunction "VDD_VDD") (pintype "bidirectional"))
      (node (ref "U$16") (pin "P1S/P2S") (pinfunction "P1S/P2S_P1S/P2S") (pintype "bidirectional"))
      (node (ref "U$17") (pin "VDD") (pinfunction "VDD_VDD") (pintype "bidirectional"))
      (node (ref "U$18") (pin "P1S/P2S") (pinfunction "P1S/P2S_P1S/P2S") (pintype "bidirectional"))
    )
    (net (code "45") (name "VMTR") (class "Default")
      (node (ref "R_VMTR_1") (pin "2") (pinfunction "2_2") (pintype "passive"))
      (node (ref "R_VMTR_2") (pin "1") (pinfunction "1_1") (pintype "passive"))
      (node (ref "U$11") (pin "1") (pinfunction "1_1") (pintype "bidirectional"))
    )
    (net (code "46") (name "unconnected-(U$15-PadNC1)") (class "Default")
      (node (ref "U$15") (pin "NC1") (pinfunction "NC1_NC1") (pintype "bidirectional"))
    )
    (net (code "47") (name "unconnected-(U$15-PadNC2)") (class "Default")
      (node (ref "U$15") (pin "NC2") (pinfunction "NC2_NC2") (pintype "bidirectional"))
    )
    (net (code "48") (name "unconnected-(U$17-PadNC1)") (class "Default")
      (node (ref "U$17") (pin "NC1") (pinfunction "NC1_NC1") (pintype "bidirectional"))
    )
    (net (code "49") (name "unconnected-(U$17-PadNC2)") (class "Default")
      (node (ref "U$17") (pin "NC2") (pinfunction "NC2_NC2") (pintype "bidirectional"))
    )
  )
)
